# USB.net
KiCad netlist of a schematic drawn in Altium Designer
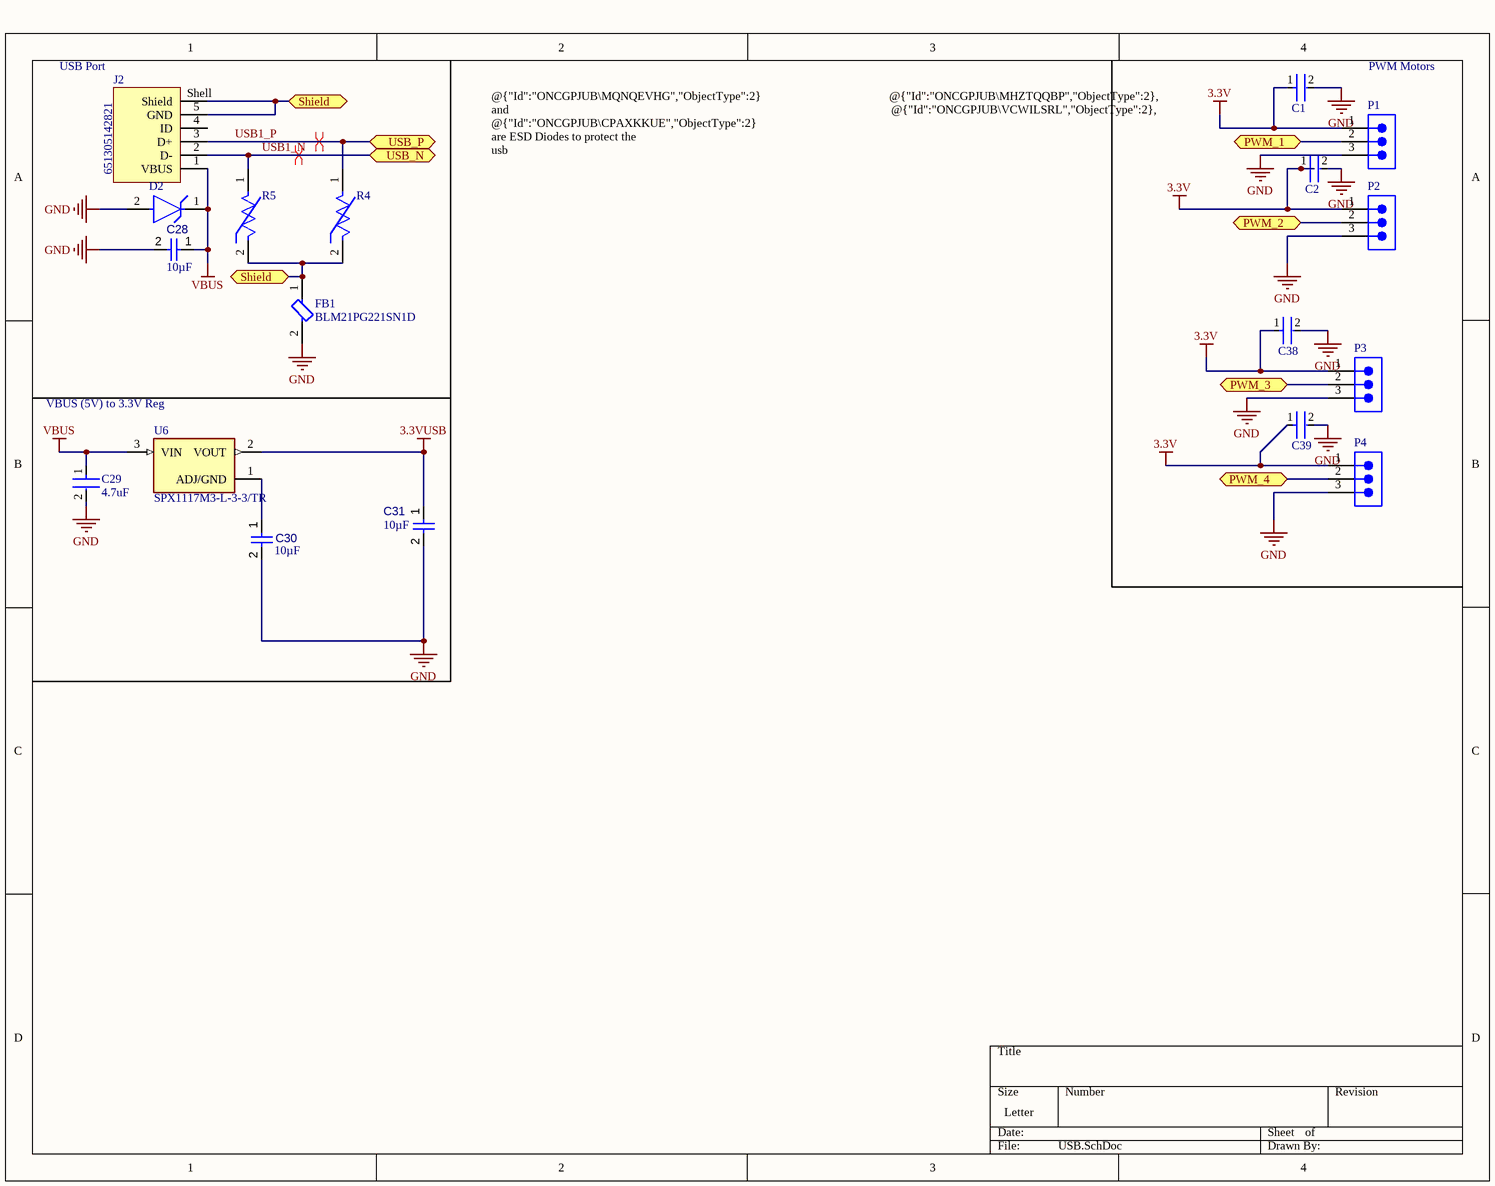
[diagram p0: USB.SchDoc]

(export (version "E")
  (design (tool "Eeschema 10.0.6"))
  (components
    (comp (ref "C1")
      (value "GRM033Z71C104KE14J")
      (footprint "FP-GRM033-0_03-IPC_A")
      (description "Chip Multilayer Ceramic Capacitors for General Purpose, 0201, 0.10uF, X7R, 15%, 10%, 16V")
      (libsource (lib "Altium Content Vault") (part "b4654b650e69147ec39a6b967a45e02"))
    )
    (comp (ref "C2")
      (value "GRM033Z71C104KE14J")
      (footprint "FP-GRM033-0_03-IPC_A")
      (description "Chip Multilayer Ceramic Capacitors for General Purpose, 0201, 0.10uF, X7R, 15%, 10%, 16V")
      (libsource (lib "Altium Content Vault") (part "b4654b650e69147ec39a6b967a45e02"))
    )
    (comp (ref "C28")
      (value "10µF")
      (footprint "CAPC0603(1608)100_L")
      (description "Chip Capacitor, 10µF +/-20%, 10V, 0603, Thickness 1 mm")
      (fields (field (name "TOLERANCE") "10%") (field (name "Comment") "Capacitor 10µF +/-20% 10V 0603"))
      (libsource (lib "George Evanisko") (part "CAP-NP-2"))
    )
    (comp (ref "C29")
      (value "4.7uF")
      (footprint "FP-RDE3P1-MFG")
      (description "RDEC72A475K3P1H03B")
      (fields (field (name "TOLERANCE") "10%"))
      (libsource (lib "Altium Content Vault") (part "RDEC72A475K3P1H03B"))
    )
    (comp (ref "C30")
      (value "10µF")
      (footprint "CAPC0603(1608)100_L")
      (description "Chip Capacitor, 10µF +/-20%, 10V, 0603, Thickness 1 mm")
      (fields (field (name "TOLERANCE") "10%") (field (name "Comment") "10uF"))
      (libsource (lib "George Evanisko") (part "CAP-NP-2"))
    )
    (comp (ref "C31")
      (value "10µF")
      (footprint "CAPC0603(1608)100_L")
      (description "Chip Capacitor, 10µF +/-20%, 10V, 0603, Thickness 1 mm")
      (fields (field (name "TOLERANCE") "10%") (field (name "Comment") "10uF"))
      (libsource (lib "George Evanisko") (part "CAP-NP-2"))
    )
    (comp (ref "C38")
      (value "GRM033Z71C104KE14J")
      (footprint "FP-GRM033-0_03-IPC_A")
      (description "Chip Multilayer Ceramic Capacitors for General Purpose, 0201, 0.10uF, X7R, 15%, 10%, 16V")
      (libsource (lib "Altium Content Vault") (part "b4654b650e69147ec39a6b967a45e02"))
    )
    (comp (ref "C39")
      (value "GRM033Z71C104KE14J")
      (footprint "FP-GRM033-0_03-IPC_A")
      (description "Chip Multilayer Ceramic Capacitors for General Purpose, 0201, 0.10uF, X7R, 15%, 10%, 16V")
      (libsource (lib "Altium Content Vault") (part "b4654b650e69147ec39a6b967a45e02"))
    )
    (comp (ref "D2")
      (value "TVS305E3")
      (footprint "FP-BODY-A-MFG")
      (description "TVS305E3 Uni-Directional Tvs A-Body Rohs Compliant: Yes")
      (libsource (lib "Altium Content Vault") (part "f813f71cba58e380607f5dd3caf9714"))
    )
    (comp (ref "FB1")
      (value "BLM21PG221SN1D")
      (footprint "FP-BLM21-0_2-t0_85-e0_5-IPC_B")
      (description "Chip Ferrite Bead, 0805, 220Ω @ 100MHz, 0.045Ω, 25%, 2A")
      (fields (field (name "TOLERANCE") "25%"))
      (libsource (lib "Altium Content Vault") (part "5f30dd21d616792df468990f7003faa"))
    )
    (comp (ref "J2")
      (value "651305142821")
      (footprint "651305142821")
      (libsource (lib "Altium Content Vault") (part "Mini USB 2.0_Type AB_Receptacle_1 Port"))
    )
    (comp (ref "P1")
      (value "61300311121")
      (footprint "61300311121")
      (libsource (lib "Altium Content Vault") (part "Header_Male_1R_03P"))
    )
    (comp (ref "P2")
      (value "61300311121")
      (footprint "61300311121")
      (libsource (lib "Altium Content Vault") (part "Header_Male_1R_03P"))
    )
    (comp (ref "P3")
      (value "61300311121")
      (footprint "61300311121")
      (libsource (lib "Altium Content Vault") (part "Header_Male_1R_03P"))
    )
    (comp (ref "P4")
      (value "61300311121")
      (footprint "61300311121")
      (libsource (lib "Altium Content Vault") (part "Header_Male_1R_03P"))
    )
    (comp (ref "R4")
      (value "CG0603MLC-05LE")
      (footprint "FP-CG0603-MFG")
      (description "VARISTOR 0603")
      (fields
        (field (name "MANUFACTURER") "Bourns Inc.")
        (field (name "OCTOPART") "https://octopart.com/cg0603mlc-05le-bourns-7576245")
      )
      (libsource (lib "Altium Content Vault") (part "78a88060d5b7b043d6e48adc4284376"))
    )
    (comp (ref "R5")
      (value "CG0603MLC-05LE")
      (footprint "FP-CG0603-MFG")
      (description "VARISTOR 0603")
      (fields
        (field (name "MANUFACTURER") "Bourns Inc.")
        (field (name "OCTOPART") "https://octopart.com/cg0603mlc-05le-bourns-7576245")
      )
      (libsource (lib "Altium Content Vault") (part "78a88060d5b7b043d6e48adc4284376"))
    )
    (comp (ref "U6")
      (value "SPX1117M3-L-3-3/TR")
      (footprint "SOT230P700X180-3N")
      (description "Linear Voltage Regulator IC Positive Fixed 1 Output 800mA SOT-223-3")
      (fields (field (name "MF") "MaxLinear"))
      (libsource (lib "George Evanisko") (part "SPX1117M3-L-3-3/TR"))
    )
  )
  (nets
    (net (code "1") (name "/PWM_1") (class "Default")
      (node (ref "P1") (pin "2") (pinfunction "2_2") (pintype "passive"))
    )
    (net (code "2") (name "/PWM_2") (class "Default")
      (node (ref "P2") (pin "2") (pinfunction "2_2") (pintype "passive"))
    )
    (net (code "3") (name "/PWM_3") (class "Default")
      (node (ref "P3") (pin "2") (pinfunction "2_2") (pintype "passive"))
    )
    (net (code "4") (name "/PWM_4") (class "Default")
      (node (ref "P4") (pin "2") (pinfunction "2_2") (pintype "passive"))
    )
    (net (code "5") (name "/Shield") (class "Default")
      (node (ref "FB1") (pin "1") (pinfunction "1_1") (pintype "passive"))
      (node (ref "J2") (pin "5") (pinfunction "GND_5") (pintype "passive"))
      (node (ref "J2") (pin "Shell") (pinfunction "Shield_Shell") (pintype "passive"))
      (node (ref "R4") (pin "2") (pinfunction "2_2") (pintype "passive"))
      (node (ref "R5") (pin "2") (pinfunction "2_2") (pintype "passive"))
    )
    (net (code "6") (name "/USB1_N") (class "Default")
      (node (ref "J2") (pin "2") (pinfunction "D-_2") (pintype "passive"))
      (node (ref "R5") (pin "1") (pinfunction "1_1") (pintype "passive"))
    )
    (net (code "7") (name "/USB1_P") (class "Default")
      (node (ref "J2") (pin "3") (pinfunction "D+_3") (pintype "passive"))
      (node (ref "R4") (pin "1") (pinfunction "1_1") (pintype "passive"))
    )
    (net (code "8") (name "3.3V") (class "Default")
      (node (ref "C1") (pin "1") (pinfunction "1_1") (pintype "passive"))
      (node (ref "C2") (pin "1") (pinfunction "1_1") (pintype "passive"))
      (node (ref "C38") (pin "1") (pinfunction "1_1") (pintype "passive"))
      (node (ref "C39") (pin "1") (pinfunction "1_1") (pintype "passive"))
      (node (ref "P1") (pin "1") (pinfunction "1_1") (pintype "passive"))
      (node (ref "P2") (pin "1") (pinfunction "1_1") (pintype "passive"))
      (node (ref "P3") (pin "1") (pinfunction "1_1") (pintype "passive"))
      (node (ref "P4") (pin "1") (pinfunction "1_1") (pintype "passive"))
    )
    (net (code "9") (name "3.3VUSB") (class "Default")
      (node (ref "C31") (pin "1") (pinfunction "1_1") (pintype "passive"))
      (node (ref "U6") (pin "2") (pinfunction "VOUT_2") (pintype "output"))
    )
    (net (code "10") (name "GND") (class "Default")
      (node (ref "C1") (pin "2") (pinfunction "2_2") (pintype "passive"))
      (node (ref "C2") (pin "2") (pinfunction "2_2") (pintype "passive"))
      (node (ref "C28") (pin "2") (pinfunction "2_2") (pintype "passive"))
      (node (ref "C29") (pin "2") (pinfunction "2_2") (pintype "passive"))
      (node (ref "C30") (pin "2") (pinfunction "2_2") (pintype "passive"))
      (node (ref "C31") (pin "2") (pinfunction "2_2") (pintype "passive"))
      (node (ref "C38") (pin "2") (pinfunction "2_2") (pintype "passive"))
      (node (ref "C39") (pin "2") (pinfunction "2_2") (pintype "passive"))
      (node (ref "D2") (pin "2") (pinfunction "A_2") (pintype "passive"))
      (node (ref "FB1") (pin "2") (pinfunction "2_2") (pintype "passive"))
      (node (ref "P1") (pin "3") (pinfunction "3_3") (pintype "passive"))
      (node (ref "P2") (pin "3") (pinfunction "3_3") (pintype "passive"))
      (node (ref "P3") (pin "3") (pinfunction "3_3") (pintype "passive"))
      (node (ref "P4") (pin "3") (pinfunction "3_3") (pintype "passive"))
    )
    (net (code "11") (name "Net-(U6-ADJ{slash}GND)") (class "Default")
      (node (ref "C30") (pin "1") (pinfunction "1_1") (pintype "passive"))
      (node (ref "U6") (pin "1") (pinfunction "ADJ/GND_1") (pintype "power_in"))
    )
    (net (code "12") (name "VBUS") (class "Default")
      (node (ref "C28") (pin "1") (pinfunction "1_1") (pintype "passive"))
      (node (ref "C29") (pin "1") (pinfunction "1_1") (pintype "passive"))
      (node (ref "D2") (pin "1") (pinfunction "C_1") (pintype "passive"))
      (node (ref "J2") (pin "1") (pinfunction "VBUS_1") (pintype "passive"))
      (node (ref "U6") (pin "3") (pinfunction "VIN_3") (pintype "input"))
    )
    (net (code "13") (name "unconnected-(J2-ID-Pad4)") (class "Default")
      (node (ref "J2") (pin "4") (pinfunction "ID_4") (pintype "passive"))
    )
  )
)
